# NiceClock.net
KiCad netlist of a schematic drawn in EAGLE
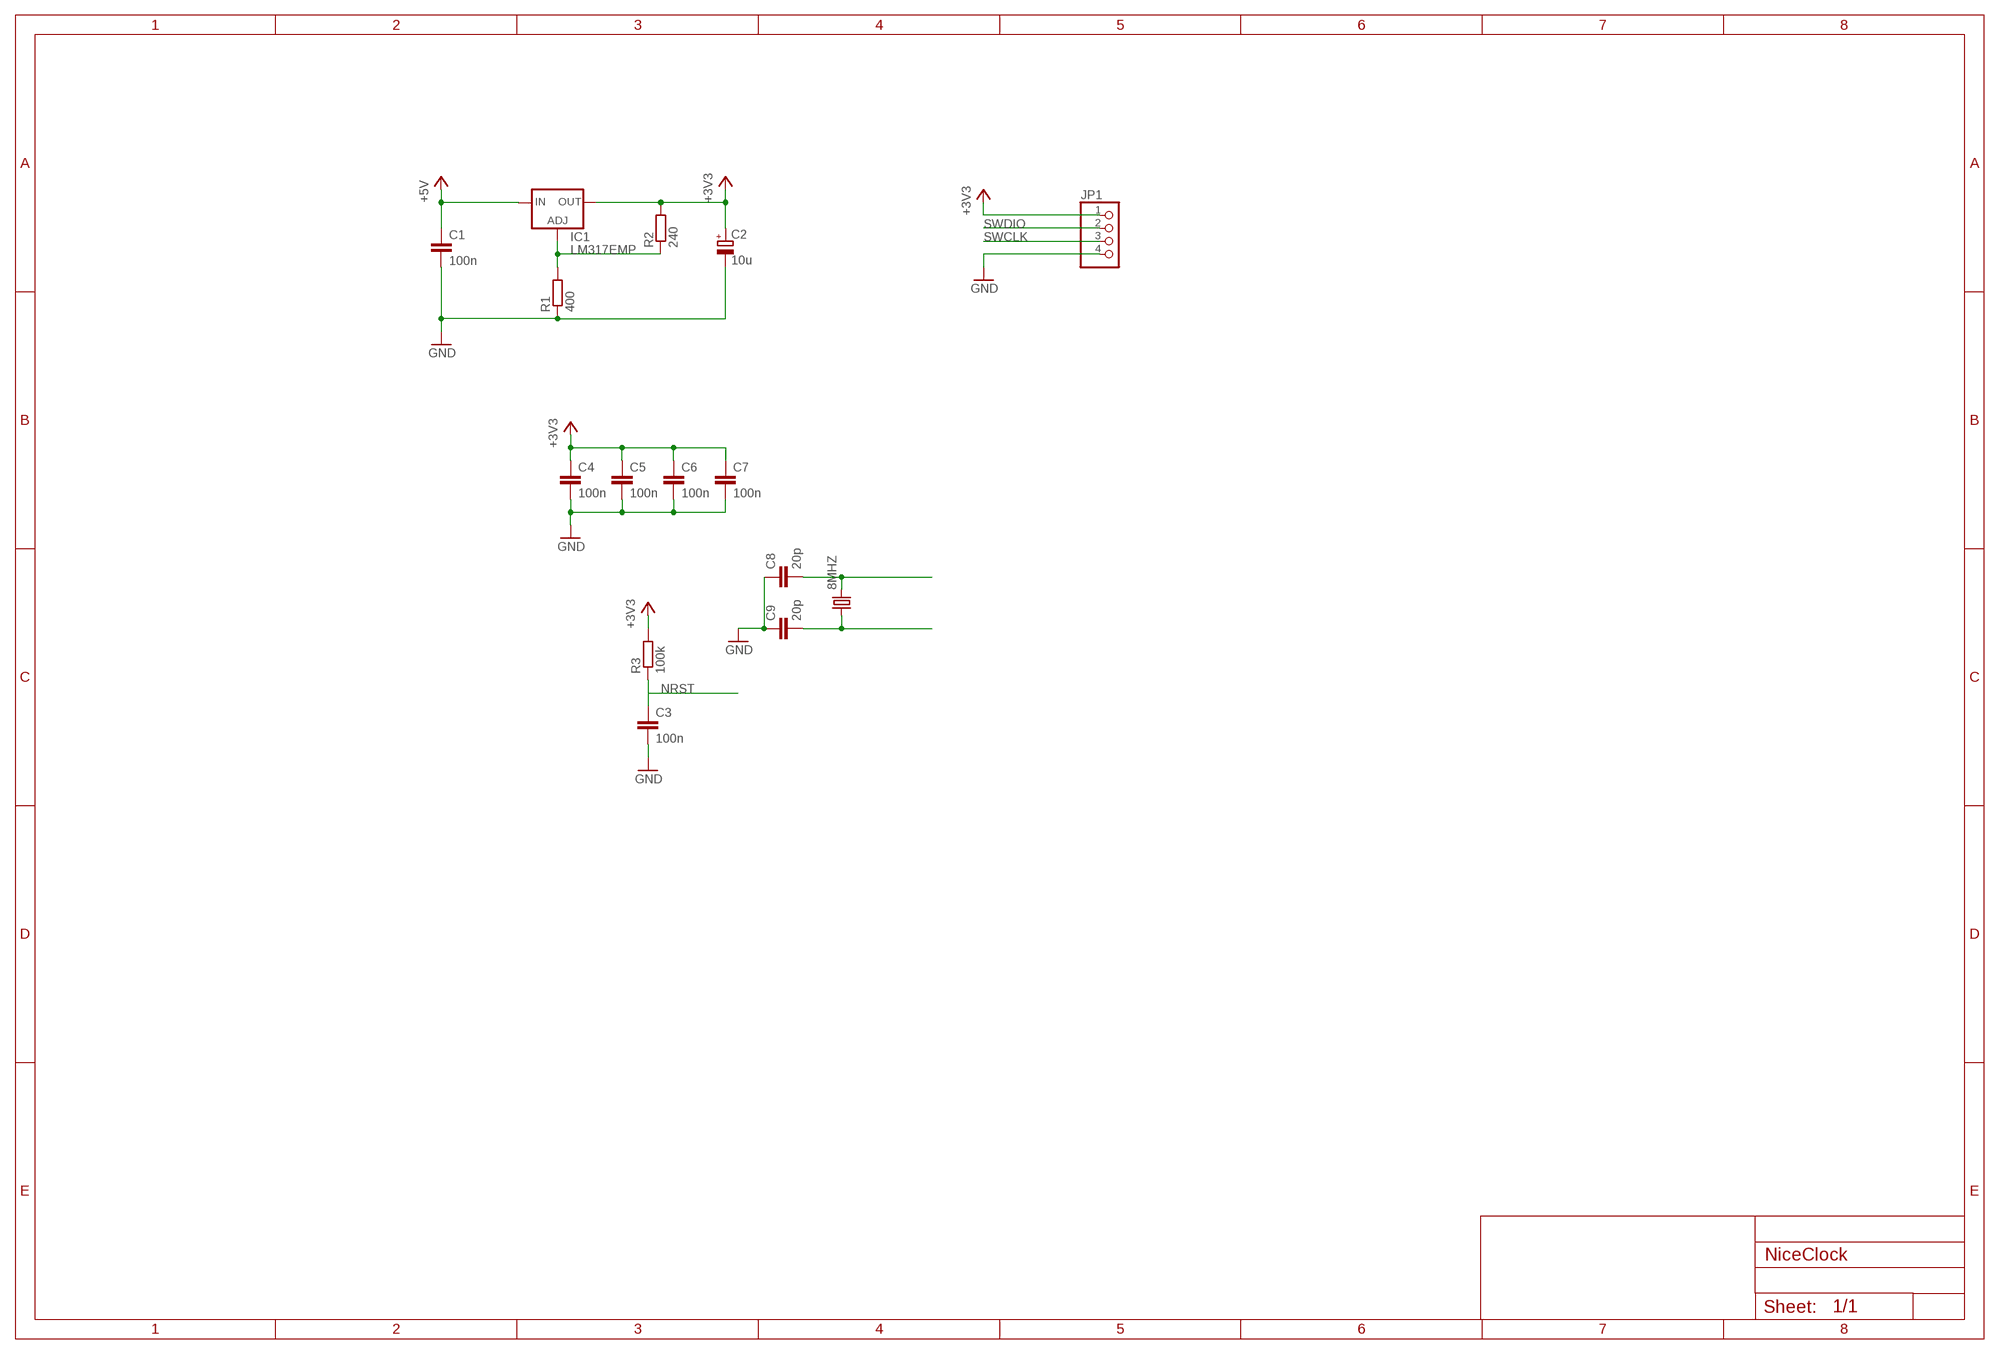
[diagram p0: schematic, sheet 1]

(export (version "E")
  (design (tool "Eeschema 10.0.6"))
  (components
    (comp (ref "8MHZ")
      (value "CRYSTALHC49UP")
      (footprint "eagle-import:HC49UP")
      (libsource (lib "eagle-import") (part "CRYSTALHC49UP"))
    )
    (comp (ref "C1")
      (value "100n")
      (footprint "eagle-import:C0603")
      (libsource (lib "eagle-import") (part "C-EUC0603"))
    )
    (comp (ref "C2")
      (value "10u")
      (footprint "eagle-import:C_6032-28W")
      (libsource (lib "eagle-import") (part "CPOL-EUC/6032-28W"))
    )
    (comp (ref "C3")
      (value "100n")
      (footprint "eagle-import:C0603")
      (libsource (lib "eagle-import") (part "C-EUC0603"))
    )
    (comp (ref "C4")
      (value "100n")
      (footprint "eagle-import:C0603")
      (libsource (lib "eagle-import") (part "C-EUC0603"))
    )
    (comp (ref "C5")
      (value "100n")
      (footprint "eagle-import:C0603")
      (libsource (lib "eagle-import") (part "C-EUC0603"))
    )
    (comp (ref "C6")
      (value "100n")
      (footprint "eagle-import:C0603")
      (libsource (lib "eagle-import") (part "C-EUC0603"))
    )
    (comp (ref "C7")
      (value "100n")
      (footprint "eagle-import:C0603")
      (libsource (lib "eagle-import") (part "C-EUC0603"))
    )
    (comp (ref "C8")
      (value "20p")
      (footprint "eagle-import:C0603")
      (libsource (lib "eagle-import") (part "C-EUC0603"))
    )
    (comp (ref "C9")
      (value "20p")
      (footprint "eagle-import:C0603")
      (libsource (lib "eagle-import") (part "C-EUC0603"))
    )
    (comp (ref "IC1")
      (value "LM317EMP")
      (footprint "eagle-import:SOT223")
      (libsource (lib "eagle-import") (part "LM317?MSTT3"))
    )
    (comp (ref "JP1")
      (value "PINHD-1X4/90")
      (footprint "eagle-import:1X04_90")
      (libsource (lib "eagle-import") (part "PINHD-1X4/90"))
    )
    (comp (ref "R1")
      (value "400")
      (footprint "eagle-import:R0603")
      (libsource (lib "eagle-import") (part "R-EU_R0603"))
    )
    (comp (ref "R2")
      (value "240")
      (footprint "eagle-import:R0603")
      (libsource (lib "eagle-import") (part "R-EU_R0603"))
    )
    (comp (ref "R3")
      (value "100k")
      (footprint "eagle-import:R0603")
      (libsource (lib "eagle-import") (part "R-EU_R0603"))
    )
  )
  (nets
    (net (code "1") (name "+3V3") (class "Default")
      (node (ref "C2") (pin "+") (pinfunction "+_+") (pintype "passive"))
      (node (ref "C4") (pin "1") (pinfunction "1_1") (pintype "passive"))
      (node (ref "C5") (pin "1") (pinfunction "1_1") (pintype "passive"))
      (node (ref "C6") (pin "1") (pinfunction "1_1") (pintype "passive"))
      (node (ref "C7") (pin "1") (pinfunction "1_1") (pintype "passive"))
      (node (ref "IC1") (pin "4") (pinfunction "OUT_4") (pintype "passive"))
      (node (ref "JP1") (pin "1") (pinfunction "1_1") (pintype "passive"))
      (node (ref "R2") (pin "2") (pinfunction "2_2") (pintype "passive"))
      (node (ref "R3") (pin "2") (pinfunction "2_2") (pintype "passive"))
    )
    (net (code "2") (name "+5V") (class "Default")
      (node (ref "C1") (pin "1") (pinfunction "1_1") (pintype "passive"))
      (node (ref "IC1") (pin "3") (pinfunction "IN_3") (pintype "input"))
    )
    (net (code "3") (name "/NRST") (class "Default")
      (node (ref "C3") (pin "1") (pinfunction "1_1") (pintype "passive"))
      (node (ref "R3") (pin "1") (pinfunction "1_1") (pintype "passive"))
    )
    (net (code "4") (name "/SWCLK") (class "Default")
      (node (ref "JP1") (pin "3") (pinfunction "3_3") (pintype "passive"))
    )
    (net (code "5") (name "/SWDIO") (class "Default")
      (node (ref "JP1") (pin "2") (pinfunction "2_2") (pintype "passive"))
    )
    (net (code "6") (name "GND") (class "Default")
      (node (ref "C1") (pin "2") (pinfunction "2_2") (pintype "passive"))
      (node (ref "C2") (pin "-") (pinfunction "-_-") (pintype "passive"))
      (node (ref "C3") (pin "2") (pinfunction "2_2") (pintype "passive"))
      (node (ref "C4") (pin "2") (pinfunction "2_2") (pintype "passive"))
      (node (ref "C5") (pin "2") (pinfunction "2_2") (pintype "passive"))
      (node (ref "C6") (pin "2") (pinfunction "2_2") (pintype "passive"))
      (node (ref "C7") (pin "2") (pinfunction "2_2") (pintype "passive"))
      (node (ref "C8") (pin "1") (pinfunction "1_1") (pintype "passive"))
      (node (ref "C9") (pin "1") (pinfunction "1_1") (pintype "passive"))
      (node (ref "JP1") (pin "4") (pinfunction "4_4") (pintype "passive"))
      (node (ref "R1") (pin "1") (pinfunction "1_1") (pintype "passive"))
    )
    (net (code "7") (name "Net-(8MHZ-Pad1)") (class "Default")
      (node (ref "8MHZ") (pin "1") (pinfunction "1_1") (pintype "passive"))
      (node (ref "C9") (pin "2") (pinfunction "2_2") (pintype "passive"))
    )
    (net (code "8") (name "Net-(8MHZ-Pad2)") (class "Default")
      (node (ref "8MHZ") (pin "2") (pinfunction "2_2") (pintype "passive"))
      (node (ref "C8") (pin "2") (pinfunction "2_2") (pintype "passive"))
    )
    (net (code "9") (name "Net-(IC1-ADJ)") (class "Default")
      (node (ref "IC1") (pin "1") (pinfunction "ADJ_1") (pintype "input"))
      (node (ref "R1") (pin "2") (pinfunction "2_2") (pintype "passive"))
      (node (ref "R2") (pin "1") (pinfunction "1_1") (pintype "passive"))
    )
  )
)
